# ttp223.net
KiCad netlist of a schematic drawn in EAGLE
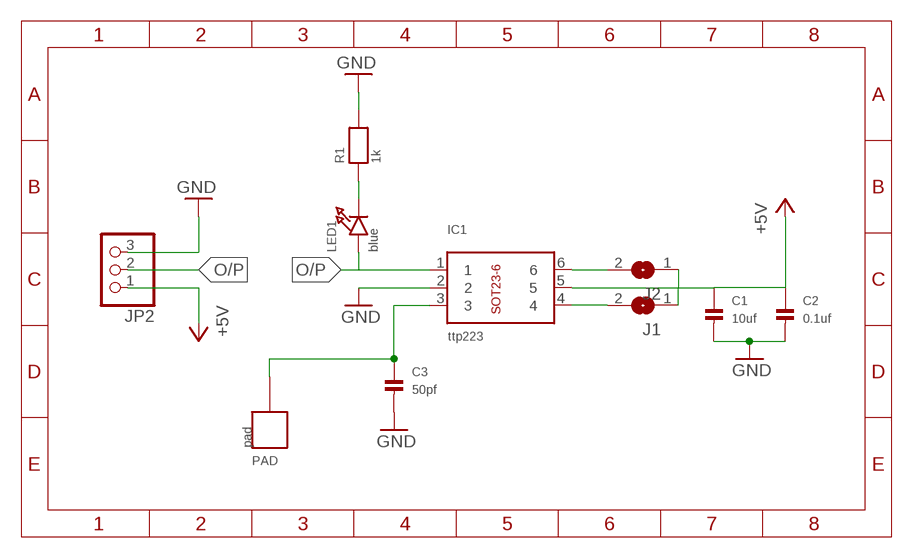
[diagram p0: schematic, sheet 1]

(export (version "E")
  (design (tool "Eeschema 10.0.6"))
  (components
    (comp (ref "C1")
      (value "10uf")
      (footprint "eagle-import:0805")
      (libsource (lib "eagle-import") (part "CAP_CERAMIC0805"))
    )
    (comp (ref "C2")
      (value "0.1uf")
      (footprint "eagle-import:0805")
      (libsource (lib "eagle-import") (part "CAP_CERAMIC0805"))
    )
    (comp (ref "C3")
      (value "50pf")
      (footprint "eagle-import:0805")
      (libsource (lib "eagle-import") (part "CAP_CERAMIC0805"))
    )
    (comp (ref "IC1")
      (value "ttp223")
      (footprint "eagle-import:BREAKOUT_SOT23-6")
      (libsource (lib "eagle-import") (part "BREAKOUT_SOT23-6"))
    )
    (comp (ref "J1")
      (value "SOLDERJUMPERREFLOW")
      (footprint "eagle-import:SOLDERJUMPER_REFLOW")
      (libsource (lib "eagle-import") (part "SOLDERJUMPERREFLOW"))
    )
    (comp (ref "J2")
      (value "SOLDERJUMPERREFLOW")
      (footprint "eagle-import:SOLDERJUMPER_REFLOW")
      (libsource (lib "eagle-import") (part "SOLDERJUMPERREFLOW"))
    )
    (comp (ref "JP2")
      (value "HEADER-1X3ROUND")
      (footprint "eagle-import:1X03_ROUND")
      (libsource (lib "eagle-import") (part "HEADER-1X3ROUND"))
    )
    (comp (ref "LED1")
      (value "blue")
      (footprint "eagle-import:CHIPLED_0805")
      (libsource (lib "eagle-import") (part "LED0805"))
    )
    (comp (ref "PAD")
      (value "pad")
      (footprint "eagle-import:CAP_TOUCHPAD")
      (libsource (lib "eagle-import") (part "CAP_TOUCHPAD"))
    )
    (comp (ref "R1")
      (value "1k")
      (footprint "eagle-import:0805")
      (libsource (lib "eagle-import") (part "RESISTOR0805"))
    )
  )
  (nets
    (net (code "1") (name "+5V") (class "Default")
      (node (ref "C1") (pin "1") (pinfunction "P$1_1") (pintype "passive"))
      (node (ref "C2") (pin "1") (pinfunction "P$1_1") (pintype "passive"))
      (node (ref "IC1") (pin "5") (pinfunction "5_5") (pintype "bidirectional"))
      (node (ref "J1") (pin "1") (pinfunction "1_1") (pintype "passive"))
      (node (ref "J2") (pin "1") (pinfunction "1_1") (pintype "passive"))
      (node (ref "JP2") (pin "1") (pinfunction "1_1") (pintype "passive"))
    )
    (net (code "2") (name "GND") (class "Default")
      (node (ref "C1") (pin "2") (pinfunction "P$2_2") (pintype "passive"))
      (node (ref "C2") (pin "2") (pinfunction "P$2_2") (pintype "passive"))
      (node (ref "C3") (pin "2") (pinfunction "P$2_2") (pintype "passive"))
      (node (ref "IC1") (pin "2") (pinfunction "2_2") (pintype "bidirectional"))
      (node (ref "JP2") (pin "3") (pinfunction "3_3") (pintype "passive"))
      (node (ref "R1") (pin "2") (pinfunction "2_2") (pintype "passive"))
    )
    (net (code "3") (name "Net-(C3-P$1)") (class "Default")
      (node (ref "C3") (pin "1") (pinfunction "P$1_1") (pintype "passive"))
      (node (ref "IC1") (pin "3") (pinfunction "3_3") (pintype "bidirectional"))
      (node (ref "PAD") (pin "P$1") (pinfunction "P$1_P$1") (pintype "bidirectional"))
    )
    (net (code "4") (name "Net-(IC1-Pad4)") (class "Default")
      (node (ref "IC1") (pin "4") (pinfunction "4_4") (pintype "bidirectional"))
      (node (ref "J1") (pin "2") (pinfunction "2_2") (pintype "passive"))
    )
    (net (code "5") (name "Net-(IC1-Pad6)") (class "Default")
      (node (ref "IC1") (pin "6") (pinfunction "6_6") (pintype "bidirectional"))
      (node (ref "J2") (pin "2") (pinfunction "2_2") (pintype "passive"))
    )
    (net (code "6") (name "Net-(LED1-PadC)") (class "Default")
      (node (ref "LED1") (pin "C") (pinfunction "C_C") (pintype "passive"))
      (node (ref "R1") (pin "1") (pinfunction "1_1") (pintype "passive"))
    )
    (net (code "7") (name "O{slash}P") (class "Default")
      (node (ref "IC1") (pin "1") (pinfunction "1_1") (pintype "bidirectional"))
      (node (ref "JP2") (pin "2") (pinfunction "2_2") (pintype "passive"))
      (node (ref "LED1") (pin "A") (pinfunction "A_A") (pintype "passive"))
    )
  )
)
